# k26_baseboard.net
KiCad netlist of a schematic drawn in Altium Designer
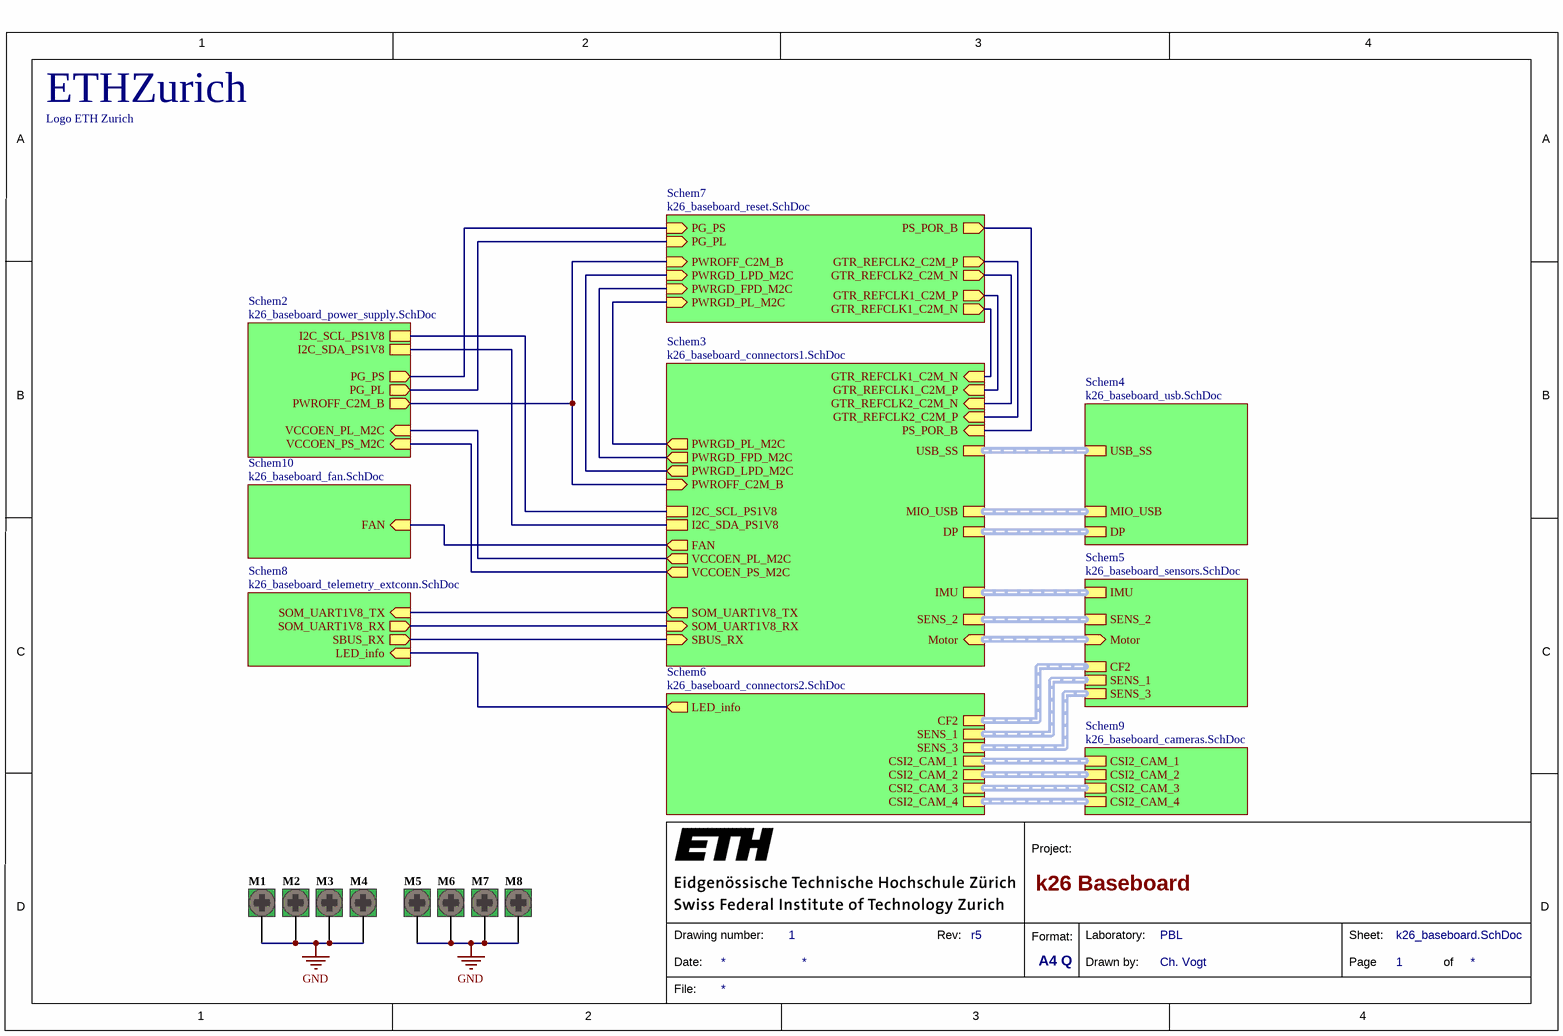
[diagram p0: k26_baseboard.SchDoc]

(export (version "E")
  (design (tool "Eeschema 10.0.6"))
  (components
    (comp (ref "A1")
      (value "Logo ETH Zurich")
      (footprint "eth-zurich_2mm")
      (libsource (lib "ETHZ Vault") (part "Logo ETH Zurich"))
    )
    (comp (ref "M1")
      (value "~")
      (footprint "Hole M3")
      (description "M3 Hole, 3.2mm drill, 6.6mm landing pads, 3.9mm pad in middle layers")
      (libsource (lib "k26_FPGA_drone_baseboard") (part "Hole"))
    )
    (comp (ref "M2")
      (value "~")
      (footprint "Hole M3")
      (description "M3 Hole, 3.2mm drill, 6.6mm landing pads, 3.9mm pad in middle layers")
      (libsource (lib "k26_FPGA_drone_baseboard") (part "Hole"))
    )
    (comp (ref "M3")
      (value "~")
      (footprint "Hole M3")
      (description "M3 Hole, 3.2mm drill, 6.6mm landing pads, 3.9mm pad in middle layers")
      (libsource (lib "k26_FPGA_drone_baseboard") (part "Hole"))
    )
    (comp (ref "M4")
      (value "~")
      (footprint "Hole M3")
      (description "M3 Hole, 3.2mm drill, 6.6mm landing pads, 3.9mm pad in middle layers")
      (libsource (lib "k26_FPGA_drone_baseboard") (part "Hole"))
    )
    (comp (ref "M5")
      (value "~")
      (footprint "Hole M3")
      (description "M3 Hole, 3.2mm drill, 6.6mm landing pads, 3.9mm pad in middle layers")
      (libsource (lib "k26_FPGA_drone_baseboard") (part "Hole"))
    )
    (comp (ref "M6")
      (value "~")
      (footprint "Hole M3")
      (description "M3 Hole, 3.2mm drill, 6.6mm landing pads, 3.9mm pad in middle layers")
      (libsource (lib "k26_FPGA_drone_baseboard") (part "Hole"))
    )
    (comp (ref "M7")
      (value "~")
      (footprint "Hole M3")
      (description "M3 Hole, 3.2mm drill, 6.6mm landing pads, 3.9mm pad in middle layers")
      (libsource (lib "k26_FPGA_drone_baseboard") (part "Hole"))
    )
    (comp (ref "M8")
      (value "~")
      (footprint "Hole M3")
      (description "M3 Hole, 3.2mm drill, 6.6mm landing pads, 3.9mm pad in middle layers")
      (libsource (lib "k26_FPGA_drone_baseboard") (part "Hole"))
    )
  )
  (nets
    (net (code "34") (name "GND") (class "Default")
      (node (ref "M1") (pin "1") (pinfunction "1_1") (pintype "passive"))
      (node (ref "M2") (pin "1") (pinfunction "1_1") (pintype "passive"))
      (node (ref "M3") (pin "1") (pinfunction "1_1") (pintype "passive"))
      (node (ref "M4") (pin "1") (pinfunction "1_1") (pintype "passive"))
      (node (ref "M5") (pin "1") (pinfunction "1_1") (pintype "passive"))
      (node (ref "M6") (pin "1") (pinfunction "1_1") (pintype "passive"))
      (node (ref "M7") (pin "1") (pinfunction "1_1") (pintype "passive"))
      (node (ref "M8") (pin "1") (pinfunction "1_1") (pintype "passive"))
    )
  )
)
